# DigiPot_breakout.net
KiCad netlist of a schematic drawn in EAGLE
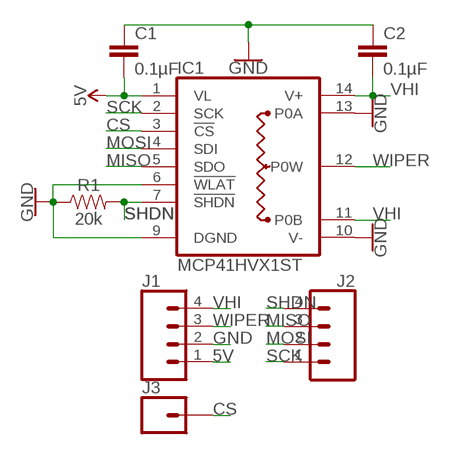
[diagram p0: schematic, sheet 1]

(export (version "E")
  (design (tool "Eeschema 10.0.6"))
  (components
    (comp (ref "C1")
      (value "0.1µF")
      (footprint "eagle-import:CAP-0.1I")
      (libsource (lib "eagle-import") (part "0.1µF-0.1''"))
    )
    (comp (ref "C2")
      (value "0.1µF")
      (footprint "eagle-import:CAP-0.1I")
      (libsource (lib "eagle-import") (part "0.1µF-0.1''"))
    )
    (comp (ref "IC1")
      (value "MCP41HVX1ST")
      (footprint "eagle-import:TSSOP14")
      (libsource (lib "eagle-import") (part "MCP41HVX1ST"))
    )
    (comp (ref "J1")
      (value "CONN_04")
      (footprint "eagle-import:1X04")
      (libsource (lib "eagle-import") (part "CONN_04"))
    )
    (comp (ref "J2")
      (value "CONN_04")
      (footprint "eagle-import:1X04")
      (libsource (lib "eagle-import") (part "CONN_04"))
    )
    (comp (ref "J3")
      (value "CONN_01")
      (footprint "eagle-import:1X01")
      (libsource (lib "eagle-import") (part "CONN_01"))
    )
    (comp (ref "R1")
      (value "20k")
      (footprint "eagle-import:AXIAL-0.3")
      (libsource (lib "eagle-import") (part "1KOHM-HORIZ-1/4W-5%"))
    )
  )
  (nets
    (net (code "1") (name "/CS") (class "Default")
      (node (ref "IC1") (pin "3") (pinfunction "~{CS}_3") (pintype "bidirectional"))
      (node (ref "J3") (pin "1") (pinfunction "1_1") (pintype "passive"))
    )
    (net (code "2") (name "/MISO") (class "Default")
      (node (ref "IC1") (pin "5") (pinfunction "SDO_5") (pintype "bidirectional"))
      (node (ref "J2") (pin "3") (pinfunction "3_3") (pintype "passive"))
    )
    (net (code "3") (name "/MOSI") (class "Default")
      (node (ref "IC1") (pin "4") (pinfunction "SDI_4") (pintype "bidirectional"))
      (node (ref "J2") (pin "2") (pinfunction "2_2") (pintype "passive"))
    )
    (net (code "4") (name "/SCK") (class "Default")
      (node (ref "IC1") (pin "2") (pinfunction "SCK_2") (pintype "bidirectional"))
      (node (ref "J2") (pin "1") (pinfunction "1_1") (pintype "passive"))
    )
    (net (code "5") (name "/SHDN") (class "Default")
      (node (ref "IC1") (pin "7") (pinfunction "~{SHDN}_7") (pintype "bidirectional"))
      (node (ref "J2") (pin "4") (pinfunction "4_4") (pintype "passive"))
      (node (ref "R1") (pin "P$2") (pinfunction "2_P$2") (pintype "passive"))
    )
    (net (code "6") (name "/VHI") (class "Default")
      (node (ref "C2") (pin "2") (pinfunction "2_2") (pintype "passive"))
      (node (ref "IC1") (pin "11") (pinfunction "P0B_11") (pintype "passive"))
      (node (ref "IC1") (pin "14") (pinfunction "V+_14") (pintype "power_in"))
      (node (ref "J1") (pin "4") (pinfunction "4_4") (pintype "passive"))
    )
    (net (code "7") (name "/WIPER") (class "Default")
      (node (ref "IC1") (pin "12") (pinfunction "P0W_12") (pintype "passive"))
      (node (ref "J1") (pin "3") (pinfunction "3_3") (pintype "passive"))
    )
    (net (code "8") (name "5V") (class "Default")
      (node (ref "C1") (pin "2") (pinfunction "2_2") (pintype "passive"))
      (node (ref "IC1") (pin "1") (pinfunction "VL_1") (pintype "power_in"))
      (node (ref "J1") (pin "1") (pinfunction "1_1") (pintype "passive"))
    )
    (net (code "9") (name "GND") (class "Default")
      (node (ref "C1") (pin "1") (pinfunction "1_1") (pintype "passive"))
      (node (ref "C2") (pin "1") (pinfunction "1_1") (pintype "passive"))
      (node (ref "IC1") (pin "10") (pinfunction "V-_10") (pintype "power_in"))
      (node (ref "IC1") (pin "13") (pinfunction "P0A_13") (pintype "passive"))
      (node (ref "IC1") (pin "6") (pinfunction "~{WLAT}_6") (pintype "bidirectional"))
      (node (ref "IC1") (pin "9") (pinfunction "DGND_9") (pintype "power_in"))
      (node (ref "J1") (pin "2") (pinfunction "2_2") (pintype "passive"))
      (node (ref "R1") (pin "P$1") (pinfunction "1_P$1") (pintype "passive"))
    )
  )
)
